# Receiver.net
KiCad netlist of a schematic drawn in Altium Designer
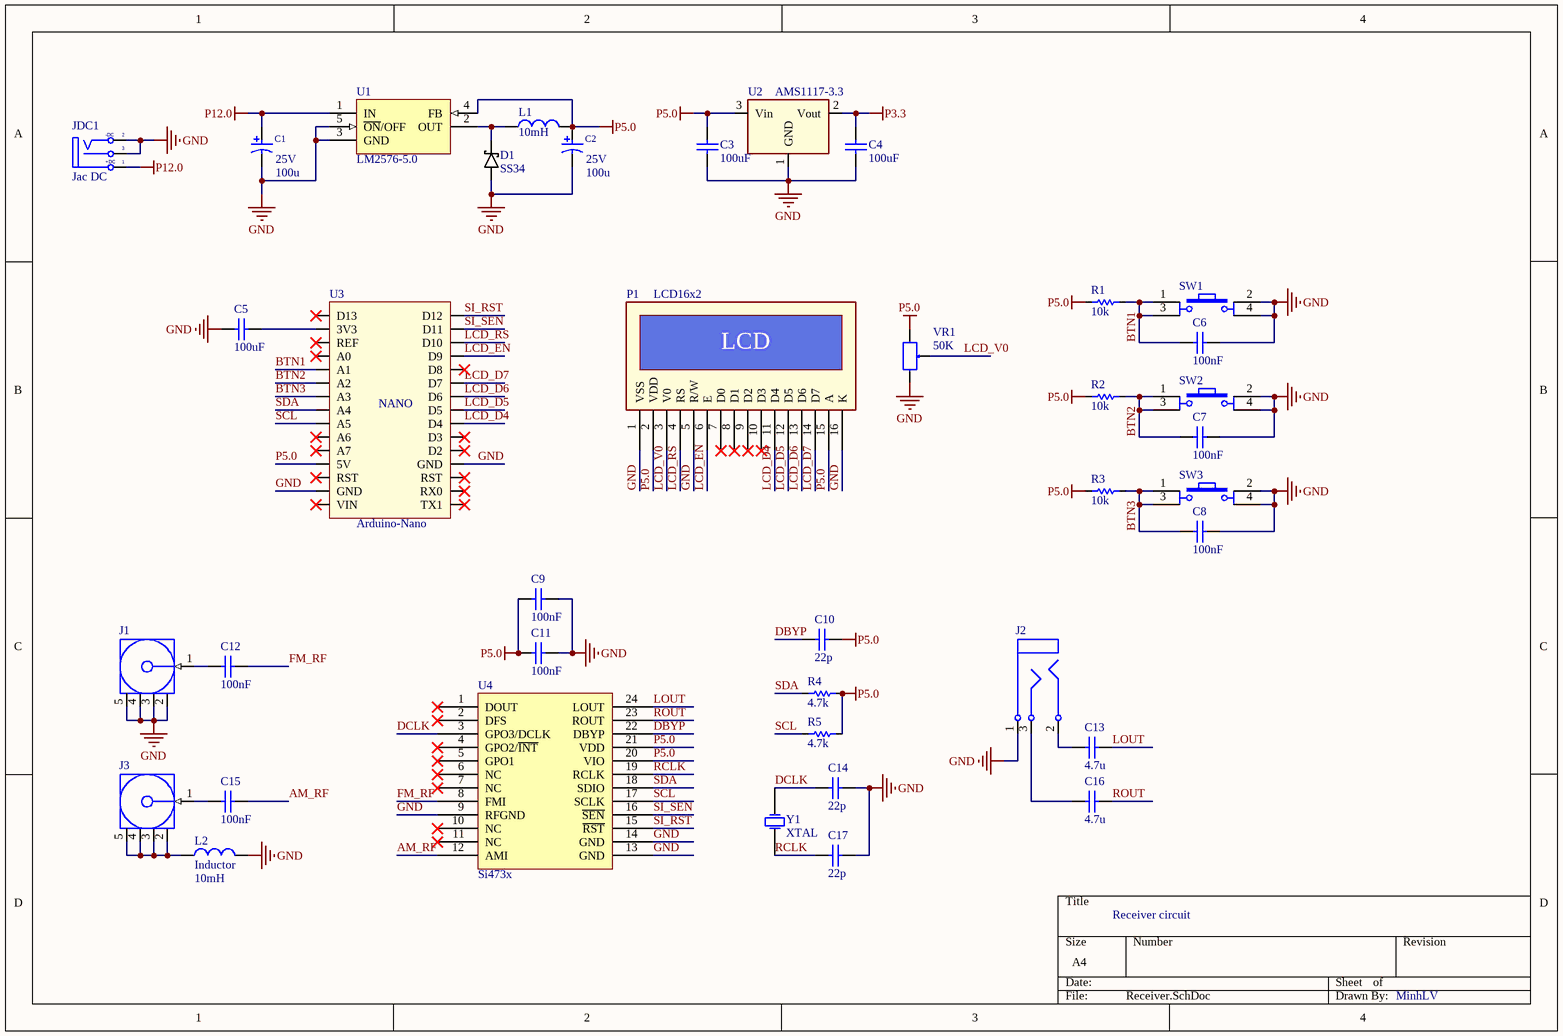
[diagram p0: Receiver.SchDoc]

(export (version "E")
  (design (tool "Eeschema 10.0.6"))
  (components
    (comp (ref "C1")
      (value "100u")
      (footprint "CAP_SMD_6_3MM")
      (description "Polarized Capacitor")
      (fields
        (field (name "MANUFACTURER") "FARNELL")
        (field (name "VOLT") "25V")
        (field (name "PUBLISHER") "Hoang Nguyen")
      )
      (libsource (lib "jmctvs") (part "Cap_Pol"))
    )
    (comp (ref "C2")
      (value "100u")
      (footprint "CAP_SMD_6_3MM")
      (description "Polarized Capacitor")
      (fields
        (field (name "MANUFACTURER") "FARNELL")
        (field (name "VOLT") "25V")
        (field (name "PUBLISHER") "Hoang Nguyen")
      )
      (libsource (lib "jmctvs") (part "Cap_Pol"))
    )
    (comp (ref "C3")
      (value "100uF")
      (footprint "CAP_SMD_0805")
      (description "Non-polarized Capacitor")
      (fields (field (name "Comment") "Cap Non-pol") (field (name "PUBLISHER") "Altium Limited"))
      (libsource (lib "jmctvs") (part "Cap Non-pol"))
    )
    (comp (ref "C4")
      (value "100uF")
      (footprint "CAP_SMD_0805")
      (description "Non-polarized Capacitor")
      (fields (field (name "Comment") "Cap Non-pol") (field (name "PUBLISHER") "Altium Limited"))
      (libsource (lib "jmctvs") (part "Cap Non-pol"))
    )
    (comp (ref "C5")
      (value "100uF")
      (footprint "CAP_SMD_0805")
      (description "Non-polarized Capacitor")
      (fields (field (name "Comment") "Cap Non-pol") (field (name "PUBLISHER") "Altium Limited"))
      (libsource (lib "jmctvs") (part "Cap Non-pol"))
    )
    (comp (ref "C6")
      (value "100nF")
      (footprint "CAP_SMD_0805")
      (description "Non-polarized Capacitor")
      (fields (field (name "Comment") "Cap Non-pol") (field (name "PUBLISHER") "Altium Limited"))
      (libsource (lib "jmctvs") (part "Cap Non-pol"))
    )
    (comp (ref "C7")
      (value "100nF")
      (footprint "CAP_SMD_0805")
      (description "Non-polarized Capacitor")
      (fields (field (name "Comment") "Cap Non-pol") (field (name "PUBLISHER") "Altium Limited"))
      (libsource (lib "jmctvs") (part "Cap Non-pol"))
    )
    (comp (ref "C8")
      (value "100nF")
      (footprint "CAP_SMD_0805")
      (description "Non-polarized Capacitor")
      (fields (field (name "Comment") "Cap Non-pol") (field (name "PUBLISHER") "Altium Limited"))
      (libsource (lib "jmctvs") (part "Cap Non-pol"))
    )
    (comp (ref "C9")
      (value "100nF")
      (footprint "CAP_SMD_0805")
      (description "Non-polarized Capacitor")
      (fields (field (name "Comment") "Cap Non-pol") (field (name "PUBLISHER") "Altium Limited"))
      (libsource (lib "jmctvs") (part "Cap Non-pol"))
    )
    (comp (ref "C10")
      (value "22p")
      (footprint "CAP_SMD_0805")
      (description "Non-polarized Capacitor")
      (fields (field (name "Comment") "Cap Non-pol") (field (name "PUBLISHER") "Altium Limited"))
      (libsource (lib "jmctvs") (part "Cap Non-pol"))
    )
    (comp (ref "C11")
      (value "100nF")
      (footprint "CAP_SMD_0805")
      (description "Non-polarized Capacitor")
      (fields (field (name "Comment") "Cap Non-pol") (field (name "PUBLISHER") "Altium Limited"))
      (libsource (lib "jmctvs") (part "Cap Non-pol"))
    )
    (comp (ref "C12")
      (value "100nF")
      (footprint "CAP_SMD_0805")
      (description "Non-polarized Capacitor")
      (fields (field (name "Comment") "Cap Non-pol") (field (name "PUBLISHER") "Altium Limited"))
      (libsource (lib "jmctvs") (part "Cap Non-pol"))
    )
    (comp (ref "C13")
      (value "4.7u")
      (footprint "CAP_SMD_0805")
      (description "Non-polarized Capacitor")
      (fields (field (name "Comment") "Cap Non-pol") (field (name "PUBLISHER") "Altium Limited"))
      (libsource (lib "jmctvs") (part "Cap Non-pol"))
    )
    (comp (ref "C14")
      (value "22p")
      (footprint "CAP_SMD_0805")
      (description "Non-polarized Capacitor")
      (fields (field (name "Comment") "Cap Non-pol") (field (name "PUBLISHER") "Altium Limited"))
      (libsource (lib "jmctvs") (part "Cap Non-pol"))
    )
    (comp (ref "C15")
      (value "100nF")
      (footprint "CAP_SMD_0805")
      (description "Non-polarized Capacitor")
      (fields (field (name "Comment") "Cap Non-pol") (field (name "PUBLISHER") "Altium Limited"))
      (libsource (lib "jmctvs") (part "Cap Non-pol"))
    )
    (comp (ref "C16")
      (value "4.7u")
      (footprint "CAP_SMD_0805")
      (description "Non-polarized Capacitor")
      (fields (field (name "Comment") "Cap Non-pol") (field (name "PUBLISHER") "Altium Limited"))
      (libsource (lib "jmctvs") (part "Cap Non-pol"))
    )
    (comp (ref "C17")
      (value "22p")
      (footprint "CAP_SMD_0805")
      (description "Non-polarized Capacitor")
      (fields (field (name "Comment") "Cap Non-pol") (field (name "PUBLISHER") "Altium Limited"))
      (libsource (lib "jmctvs") (part "Cap Non-pol"))
    )
    (comp (ref "D1")
      (value "SS34")
      (footprint "jmctvs:DO-214AC,SMA")
      (libsource (lib "jmctvs") (part "DIODE S"))
    )
    (comp (ref "J1")
      (value "SMA Connector")
      (footprint "SMA-CONNECTOR")
      (description "SMA Connector Jack, Female Socket 50Ohm Surface Mount, Right Angle Solder")
      (fields (field (name "MP") "SMA-J-P-GF-RA-SM1") (field (name "MF") "Samtec"))
      (libsource (lib "jmctvs") (part "SMA Connector"))
    )
    (comp (ref "J2")
      (value "CON.AudioJack Stereo")
      (footprint "SJ-3523-SMT")
      (description "AUDIO JACK 3.5MM STEREO SMD")
      (fields (field (name "PUBLISHER") "Altium Limited"))
      (libsource (lib "jmctvs") (part "CON.AudioJack Stereo"))
    )
    (comp (ref "J3")
      (value "SMA Connector")
      (footprint "SMA-CONNECTOR")
      (description "SMA Connector Jack, Female Socket 50Ohm Surface Mount, Right Angle Solder")
      (fields (field (name "MP") "SMA-J-P-GF-RA-SM1") (field (name "MF") "Samtec"))
      (libsource (lib "jmctvs") (part "SMA Connector"))
    )
    (comp (ref "JDC1")
      (value "Jac DC")
      (footprint "DC-IN")
      (description "Jac DC input")
      (libsource (lib "jmctvs") (part "DCIN"))
    )
    (comp (ref "L1")
      (value "10mH")
      (footprint "CDRH104")
      (description "Inductor")
      (fields (field (name "PUBLISHER") "Altium Limited"))
      (libsource (lib "jmctvs") (part "Inductor"))
    )
    (comp (ref "L2")
      (value "Inductor")
      (footprint "CDRH104")
      (fields (field (name "ALTIUM_VALUE") "10mH") (field (name "PUBLISHER") "Altium Limited"))
      (libsource (lib "jmctvs") (part "Inductor"))
    )
    (comp (ref "P1") (value "LCD16x2") (footprint "LCD16x2") (libsource (lib "jmctvs") (part "LCD Text")))
    (comp (ref "R1")
      (value "10k")
      (footprint "RES_SMD_0805")
      (description "Resistor")
      (fields (field (name "Comment") "RESISTOR") (field (name "PUBLISHER") "Altium Limited"))
      (libsource (lib "jmctvs") (part "RESISTOR"))
    )
    (comp (ref "R2")
      (value "10k")
      (footprint "RES_SMD_0805")
      (description "Resistor")
      (fields (field (name "Comment") "RESISTOR") (field (name "PUBLISHER") "Altium Limited"))
      (libsource (lib "jmctvs") (part "RESISTOR"))
    )
    (comp (ref "R3")
      (value "10k")
      (footprint "RES_SMD_0805")
      (description "Resistor")
      (fields (field (name "Comment") "RESISTOR") (field (name "PUBLISHER") "Altium Limited"))
      (libsource (lib "jmctvs") (part "RESISTOR"))
    )
    (comp (ref "R4")
      (value "4.7k")
      (footprint "RES_SMD_0805")
      (description "Resistor")
      (fields (field (name "Comment") "RESISTOR") (field (name "PUBLISHER") "Altium Limited"))
      (libsource (lib "jmctvs") (part "RESISTOR"))
    )
    (comp (ref "R5")
      (value "4.7k")
      (footprint "RES_SMD_0805")
      (description "Resistor")
      (fields (field (name "Comment") "RESISTOR") (field (name "PUBLISHER") "Altium Limited"))
      (libsource (lib "jmctvs") (part "RESISTOR"))
    )
    (comp (ref "SW1")
      (value "SW")
      (footprint "SW4")
      (description "Switch button 4 pin")
      (libsource (lib "jmctvs") (part "SW4"))
    )
    (comp (ref "SW2")
      (value "SW")
      (footprint "SW4")
      (description "Switch button 4 pin")
      (libsource (lib "jmctvs") (part "SW4"))
    )
    (comp (ref "SW3")
      (value "SW")
      (footprint "SW4")
      (description "Switch button 4 pin")
      (libsource (lib "jmctvs") (part "SW4"))
    )
    (comp (ref "U1")
      (value "LM2576-5.0")
      (footprint "jmctvs:LM2576_SMD")
      (description "Simple Switcher 3A Step Down Voltage Regulator")
      (fields (field (name "PUBLISHER") "Altium Limited"))
      (libsource (lib "jmctvs") (part "LM2576"))
    )
    (comp (ref "U2")
      (value "AMS1117-3.3")
      (footprint "SOT223")
      (description "Regulator SMD Chip")
      (fields (field (name "DESIGNED BY") "John MacTavish"))
      (libsource (lib "jmctvs") (part "AMS1117"))
    )
    (comp (ref "U3")
      (value "Arduino-Nano")
      (footprint "jmctvs:Arduino Nano")
      (description "Arduino NANO")
      (libsource (lib "jmctvs") (part "Arduino Nano"))
    )
    (comp (ref "U4") (value "Si473x") (footprint "SSOP-24") (libsource (lib "jmctvs") (part "Si473x")))
    (comp (ref "VR1")
      (value "50K")
      (footprint "VR")
      (description "Var Resistor")
      (libsource (lib "jmctvs") (part "VR"))
    )
    (comp (ref "Y1")
      (value "XTAL")
      (footprint "XT32k")
      (description "Crystal Oscillator")
      (fields (field (name "PUBLISHER") "Altium Limited"))
      (libsource (lib "jmctvs") (part "XTAL"))
    )
  )
  (nets
    (net (code "1") (name "/AM_RF") (class "Default")
      (node (ref "C15") (pin "2") (pinfunction "2_2") (pintype "passive"))
      (node (ref "U4") (pin "12") (pinfunction "AMI_12") (pintype "passive"))
    )
    (net (code "2") (name "/BTN1") (class "Default")
      (node (ref "C6") (pin "2") (pinfunction "2_2") (pintype "passive"))
      (node (ref "R1") (pin "2") (pinfunction "2_2") (pintype "passive"))
      (node (ref "SW1") (pin "1") (pintype "passive"))
      (node (ref "SW1") (pin "3") (pintype "passive"))
      (node (ref "U3") (pin "A1") (pinfunction "A1_A1") (pintype "passive"))
    )
    (net (code "3") (name "/BTN2") (class "Default")
      (node (ref "C7") (pin "2") (pinfunction "2_2") (pintype "passive"))
      (node (ref "R2") (pin "2") (pinfunction "2_2") (pintype "passive"))
      (node (ref "SW2") (pin "1") (pintype "passive"))
      (node (ref "SW2") (pin "3") (pintype "passive"))
      (node (ref "U3") (pin "A2") (pinfunction "A2_A2") (pintype "passive"))
    )
    (net (code "4") (name "/BTN3") (class "Default")
      (node (ref "C8") (pin "2") (pinfunction "2_2") (pintype "passive"))
      (node (ref "R3") (pin "2") (pinfunction "2_2") (pintype "passive"))
      (node (ref "SW3") (pin "1") (pintype "passive"))
      (node (ref "SW3") (pin "3") (pintype "passive"))
      (node (ref "U3") (pin "A3") (pinfunction "A3_A3") (pintype "passive"))
    )
    (net (code "5") (name "/DBYP") (class "Default")
      (node (ref "C10") (pin "2") (pinfunction "2_2") (pintype "passive"))
      (node (ref "U4") (pin "22") (pinfunction "DBYP_22") (pintype "passive"))
    )
    (net (code "6") (name "/DCLK") (class "Default")
      (node (ref "C14") (pin "2") (pinfunction "2_2") (pintype "passive"))
      (node (ref "U4") (pin "3") (pinfunction "GPO3/DCLK_3") (pintype "passive"))
      (node (ref "Y1") (pin "1") (pinfunction "OSC1_1") (pintype "passive"))
    )
    (net (code "7") (name "/FM_RF") (class "Default")
      (node (ref "C12") (pin "2") (pinfunction "2_2") (pintype "passive"))
      (node (ref "U4") (pin "8") (pinfunction "FMI_8") (pintype "passive"))
    )
    (net (code "8") (name "/LCD_D4") (class "Default")
      (node (ref "P1") (pin "11") (pinfunction "D4_11") (pintype "passive"))
      (node (ref "U3") (pin "D4") (pinfunction "D4_D4") (pintype "passive"))
    )
    (net (code "9") (name "/LCD_D5") (class "Default")
      (node (ref "P1") (pin "12") (pinfunction "D5_12") (pintype "passive"))
      (node (ref "U3") (pin "D5") (pinfunction "D5_D5") (pintype "passive"))
    )
    (net (code "10") (name "/LCD_D6") (class "Default")
      (node (ref "P1") (pin "13") (pinfunction "D6_13") (pintype "passive"))
      (node (ref "U3") (pin "D6") (pinfunction "D6_D6") (pintype "passive"))
    )
    (net (code "11") (name "/LCD_D7") (class "Default")
      (node (ref "P1") (pin "14") (pinfunction "D7_14") (pintype "passive"))
      (node (ref "U3") (pin "D7") (pinfunction "D7_D7") (pintype "passive"))
    )
    (net (code "12") (name "/LCD_EN") (class "Default")
      (node (ref "P1") (pin "6") (pinfunction "E_6") (pintype "passive"))
      (node (ref "U3") (pin "D9") (pinfunction "D9_D9") (pintype "passive"))
    )
    (net (code "13") (name "/LCD_RS") (class "Default")
      (node (ref "P1") (pin "4") (pinfunction "RS_4") (pintype "passive"))
      (node (ref "U3") (pin "D10") (pinfunction "D10_D10") (pintype "passive"))
    )
    (net (code "14") (name "/LCD_V0") (class "Default")
      (node (ref "P1") (pin "3") (pinfunction "V0_3") (pintype "passive"))
      (node (ref "VR1") (pin "2") (pinfunction "2_2") (pintype "passive"))
    )
    (net (code "15") (name "/LOUT") (class "Default")
      (node (ref "C13") (pin "1") (pinfunction "1_1") (pintype "passive"))
      (node (ref "U4") (pin "24") (pinfunction "LOUT_24") (pintype "passive"))
    )
    (net (code "16") (name "/RCLK") (class "Default")
      (node (ref "C17") (pin "2") (pinfunction "2_2") (pintype "passive"))
      (node (ref "U4") (pin "19") (pinfunction "RCLK_19") (pintype "passive"))
      (node (ref "Y1") (pin "2") (pinfunction "OSC2_2") (pintype "passive"))
    )
    (net (code "17") (name "/ROUT") (class "Default")
      (node (ref "C16") (pin "1") (pinfunction "1_1") (pintype "passive"))
      (node (ref "U4") (pin "23") (pinfunction "ROUT_23") (pintype "passive"))
    )
    (net (code "18") (name "/SCL") (class "Default")
      (node (ref "R5") (pin "1") (pinfunction "1_1") (pintype "passive"))
      (node (ref "U3") (pin "A5") (pinfunction "A5_A5") (pintype "passive"))
      (node (ref "U4") (pin "17") (pinfunction "SCLK_17") (pintype "passive"))
    )
    (net (code "19") (name "/SDA") (class "Default")
      (node (ref "R4") (pin "1") (pinfunction "1_1") (pintype "passive"))
      (node (ref "U3") (pin "A4") (pinfunction "A4_A4") (pintype "passive"))
      (node (ref "U4") (pin "18") (pinfunction "SDIO_18") (pintype "passive"))
    )
    (net (code "20") (name "/SI_RST") (class "Default")
      (node (ref "U3") (pin "D12") (pinfunction "D12_D12") (pintype "passive"))
      (node (ref "U4") (pin "15") (pinfunction "~{RST}_15") (pintype "passive"))
    )
    (net (code "21") (name "/SI_SEN") (class "Default")
      (node (ref "U3") (pin "D11") (pinfunction "D11_D11") (pintype "passive"))
      (node (ref "U4") (pin "16") (pinfunction "~{SEN}_16") (pintype "passive"))
    )
    (net (code "22") (name "GND") (class "Default")
      (node (ref "C1") (pin "2") (pinfunction "2_2") (pintype "passive"))
      (node (ref "C11") (pin "2") (pinfunction "2_2") (pintype "passive"))
      (node (ref "C14") (pin "1") (pinfunction "1_1") (pintype "passive"))
      (node (ref "C17") (pin "1") (pinfunction "1_1") (pintype "passive"))
      (node (ref "C2") (pin "2") (pinfunction "2_2") (pintype "passive"))
      (node (ref "C3") (pin "1") (pinfunction "1_1") (pintype "passive"))
      (node (ref "C4") (pin "1") (pinfunction "1_1") (pintype "passive"))
      (node (ref "C5") (pin "1") (pinfunction "1_1") (pintype "passive"))
      (node (ref "C6") (pin "1") (pinfunction "1_1") (pintype "passive"))
      (node (ref "C7") (pin "1") (pinfunction "1_1") (pintype "passive"))
      (node (ref "C8") (pin "1") (pinfunction "1_1") (pintype "passive"))
      (node (ref "C9") (pin "2") (pinfunction "2_2") (pintype "passive"))
      (node (ref "D1") (pin "1") (pinfunction "A_1") (pintype "passive"))
      (node (ref "J1") (pin "2") (pinfunction "GND_2") (pintype "power_in"))
      (node (ref "J1") (pin "3") (pinfunction "GND_3") (pintype "power_in"))
      (node (ref "J1") (pin "4") (pinfunction "GND_4") (pintype "power_in"))
      (node (ref "J1") (pin "5") (pinfunction "GND_5") (pintype "power_in"))
      (node (ref "J2") (pin "1") (pinfunction "1_1") (pintype "passive"))
      (node (ref "JDC1") (pin "2") (pinfunction "TN_2") (pintype "passive"))
      (node (ref "JDC1") (pin "3") (pinfunction "S_3") (pintype "power_in"))
      (node (ref "L2") (pin "2") (pinfunction "2_2") (pintype "passive"))
      (node (ref "P1") (pin "1") (pinfunction "VSS_1") (pintype "passive"))
      (node (ref "P1") (pin "16") (pinfunction "K_16") (pintype "passive"))
      (node (ref "P1") (pin "5") (pinfunction "R/W_5") (pintype "passive"))
      (node (ref "SW1") (pin "2") (pintype "passive"))
      (node (ref "SW1") (pin "4") (pintype "passive"))
      (node (ref "SW2") (pin "2") (pintype "passive"))
      (node (ref "SW2") (pin "4") (pintype "passive"))
      (node (ref "SW3") (pin "2") (pintype "passive"))
      (node (ref "SW3") (pin "4") (pintype "passive"))
      (node (ref "U1") (pin "3") (pinfunction "GND_3") (pintype "power_in"))
      (node (ref "U1") (pin "5") (pinfunction "~{ON}/OFF_5") (pintype "input"))
      (node (ref "U2") (pin "1") (pinfunction "GND_1") (pintype "passive"))
      (node (ref "U3") (pin "GND") (pinfunction "GND_GND") (pintype "passive"))
      (node (ref "U4") (pin "13") (pinfunction "GND_13") (pintype "passive"))
      (node (ref "U4") (pin "14") (pinfunction "GND_14") (pintype "passive"))
      (node (ref "U4") (pin "9") (pinfunction "RFGND_9") (pintype "passive"))
      (node (ref "VR1") (pin "3") (pinfunction "3_3") (pintype "passive"))
    )
    (net (code "23") (name "Net-(C5-Pad2)") (class "Default")
      (node (ref "C5") (pin "2") (pinfunction "2_2") (pintype "passive"))
      (node (ref "U3") (pin "3V3") (pinfunction "3V3_3V3") (pintype "passive"))
    )
    (net (code "24") (name "Net-(C13-Pad2)") (class "Default")
      (node (ref "C13") (pin "2") (pinfunction "2_2") (pintype "passive"))
      (node (ref "J2") (pin "2") (pinfunction "2_2") (pintype "passive"))
    )
    (net (code "25") (name "Net-(C16-Pad2)") (class "Default")
      (node (ref "C16") (pin "2") (pinfunction "2_2") (pintype "passive"))
      (node (ref "J2") (pin "3") (pinfunction "3_3") (pintype "passive"))
    )
    (net (code "26") (name "Net-(D1-K)") (class "Default")
      (node (ref "D1") (pin "2") (pinfunction "K_2") (pintype "passive"))
      (node (ref "L1") (pin "1") (pinfunction "1_1") (pintype "passive"))
      (node (ref "U1") (pin "2") (pinfunction "OUT_2") (pintype "power_in"))
    )
    (net (code "27") (name "Net-(J1-Signal)") (class "Default")
      (node (ref "C12") (pin "1") (pinfunction "1_1") (pintype "passive"))
      (node (ref "J1") (pin "1") (pinfunction "Signal_1") (pintype "input"))
    )
    (net (code "28") (name "Net-(J3-GND-Pad2)") (class "Default")
      (node (ref "J3") (pin "2") (pinfunction "GND_2") (pintype "power_in"))
      (node (ref "J3") (pin "3") (pinfunction "GND_3") (pintype "power_in"))
      (node (ref "J3") (pin "4") (pinfunction "GND_4") (pintype "power_in"))
      (node (ref "J3") (pin "5") (pinfunction "GND_5") (pintype "power_in"))
      (node (ref "L2") (pin "1") (pinfunction "1_1") (pintype "passive"))
    )
    (net (code "29") (name "Net-(J3-Signal)") (class "Default")
      (node (ref "C15") (pin "1") (pinfunction "1_1") (pintype "passive"))
      (node (ref "J3") (pin "1") (pinfunction "Signal_1") (pintype "input"))
    )
    (net (code "30") (name "P3.3") (class "Default")
      (node (ref "C4") (pin "2") (pinfunction "2_2") (pintype "passive"))
      (node (ref "U2") (pin "2") (pinfunction "Vout_2") (pintype "passive"))
    )
    (net (code "31") (name "P5.0") (class "Default")
      (node (ref "C10") (pin "1") (pinfunction "1_1") (pintype "passive"))
      (node (ref "C11") (pin "1") (pinfunction "1_1") (pintype "passive"))
      (node (ref "C2") (pin "1") (pinfunction "1_1") (pintype "passive"))
      (node (ref "C3") (pin "2") (pinfunction "2_2") (pintype "passive"))
      (node (ref "C9") (pin "1") (pinfunction "1_1") (pintype "passive"))
      (node (ref "L1") (pin "2") (pinfunction "2_2") (pintype "passive"))
      (node (ref "P1") (pin "15") (pinfunction "A_15") (pintype "passive"))
      (node (ref "P1") (pin "2") (pinfunction "VDD_2") (pintype "passive"))
      (node (ref "R1") (pin "1") (pinfunction "1_1") (pintype "passive"))
      (node (ref "R2") (pin "1") (pinfunction "1_1") (pintype "passive"))
      (node (ref "R3") (pin "1") (pinfunction "1_1") (pintype "passive"))
      (node (ref "R4") (pin "2") (pinfunction "2_2") (pintype "passive"))
      (node (ref "R5") (pin "2") (pinfunction "2_2") (pintype "passive"))
      (node (ref "U1") (pin "4") (pinfunction "FB_4") (pintype "input"))
      (node (ref "U2") (pin "3") (pinfunction "Vin_3") (pintype "passive"))
      (node (ref "U3") (pin "5V") (pinfunction "5V_5V") (pintype "passive"))
      (node (ref "U4") (pin "20") (pinfunction "VIO_20") (pintype "passive"))
      (node (ref "U4") (pin "21") (pinfunction "VDD_21") (pintype "passive"))
      (node (ref "VR1") (pin "1") (pinfunction "1_1") (pintype "passive"))
    )
    (net (code "32") (name "P12.0") (class "Default")
      (node (ref "C1") (pin "1") (pinfunction "1_1") (pintype "passive"))
      (node (ref "JDC1") (pin "1") (pinfunction "T_1") (pintype "passive"))
      (node (ref "U1") (pin "1") (pinfunction "IN_1") (pintype "power_in"))
    )
    (net (code "33") (name "unconnected-(P1-D0-Pad7)") (class "Default")
      (node (ref "P1") (pin "7") (pinfunction "D0_7") (pintype "passive+no_connect"))
    )
    (net (code "34") (name "unconnected-(P1-D1-Pad8)") (class "Default")
      (node (ref "P1") (pin "8") (pinfunction "D1_8") (pintype "passive+no_connect"))
    )
    (net (code "35") (name "unconnected-(P1-D2-Pad9)") (class "Default")
      (node (ref "P1") (pin "9") (pinfunction "D2_9") (pintype "passive+no_connect"))
    )
    (net (code "36") (name "unconnected-(P1-D3-Pad10)") (class "Default")
      (node (ref "P1") (pin "10") (pinfunction "D3_10") (pintype "passive+no_connect"))
    )
    (net (code "37") (name "unconnected-(U3-PadA0)") (class "Default")
      (node (ref "U3") (pin "A0") (pinfunction "A0_A0") (pintype "passive+no_connect"))
    )
    (net (code "38") (name "unconnected-(U3-PadA6)") (class "Default")
      (node (ref "U3") (pin "A6") (pinfunction "A6_A6") (pintype "passive+no_connect"))
    )
    (net (code "39") (name "unconnected-(U3-PadA7)") (class "Default")
      (node (ref "U3") (pin "A7") (pinfunction "A7_A7") (pintype "passive+no_connect"))
    )
    (net (code "40") (name "unconnected-(U3-PadD2)") (class "Default")
      (node (ref "U3") (pin "D2") (pinfunction "D2_D2") (pintype "passive+no_connect"))
    )
    (net (code "41") (name "unconnected-(U3-PadD3)") (class "Default")
      (node (ref "U3") (pin "D3") (pinfunction "D3_D3") (pintype "passive+no_connect"))
    )
    (net (code "42") (name "unconnected-(U3-PadD8)") (class "Default")
      (node (ref "U3") (pin "D8") (pinfunction "D8_D8") (pintype "passive+no_connect"))
    )
    (net (code "43") (name "unconnected-(U3-PadD13)") (class "Default")
      (node (ref "U3") (pin "D13") (pinfunction "D13_D13") (pintype "passive+no_connect"))
    )
    (net (code "44") (name "unconnected-(U3-PadREF)") (class "Default")
      (node (ref "U3") (pin "REF") (pinfunction "REF_REF") (pintype "passive+no_connect"))
    )
    (net (code "45") (name "unconnected-(U3-PadRST)") (class "Default")
      (node (ref "U3") (pin "RST") (pinfunction "RST_RST") (pintype "passive+no_connect"))
    )
    (net (code "46") (name "unconnected-(U3-PadRST)_1") (class "Default")
      (node (ref "U3") (pin "RST") (pinfunction "RST_RST") (pintype "passive+no_connect"))
    )
    (net (code "47") (name "unconnected-(U3-PadRX0)") (class "Default")
      (node (ref "U3") (pin "RX0") (pinfunction "RX0_RX0") (pintype "passive+no_connect"))
    )
    (net (code "48") (name "unconnected-(U3-PadTX1)") (class "Default")
      (node (ref "U3") (pin "TX1") (pinfunction "TX1_TX1") (pintype "passive+no_connect"))
    )
    (net (code "49") (name "unconnected-(U3-PadVIN)") (class "Default")
      (node (ref "U3") (pin "VIN") (pinfunction "VIN_VIN") (pintype "passive+no_connect"))
    )
    (net (code "50") (name "unconnected-(U4-DFS-Pad2)") (class "Default")
      (node (ref "U4") (pin "2") (pinfunction "DFS_2") (pintype "passive+no_connect"))
    )
    (net (code "51") (name "unconnected-(U4-DOUT-Pad1)") (class "Default")
      (node (ref "U4") (pin "1") (pinfunction "DOUT_1") (pintype "passive+no_connect"))
    )
    (net (code "52") (name "unconnected-(U4-GPO1-Pad5)") (class "Default")
      (node (ref "U4") (pin "5") (pinfunction "GPO1_5") (pintype "passive+no_connect"))
    )
    (net (code "53") (name "unconnected-(U4-GPO2{slash}~{INT}-Pad4)") (class "Default")
      (node (ref "U4") (pin "4") (pinfunction "GPO2/~{INT}_4") (pintype "passive+no_connect"))
    )
    (net (code "54") (name "unconnected-(U4-NC-Pad6)") (class "Default")
      (node (ref "U4") (pin "6") (pinfunction "NC_6") (pintype "passive+no_connect"))
    )
    (net (code "55") (name "unconnected-(U4-NC-Pad7)") (class "Default")
      (node (ref "U4") (pin "7") (pinfunction "NC_7") (pintype "passive+no_connect"))
    )
    (net (code "56") (name "unconnected-(U4-NC-Pad10)") (class "Default")
      (node (ref "U4") (pin "10") (pinfunction "NC_10") (pintype "passive+no_connect"))
    )
    (net (code "57") (name "unconnected-(U4-NC-Pad11)") (class "Default")
      (node (ref "U4") (pin "11") (pinfunction "NC_11") (pintype "passive+no_connect"))
    )
  )
)
